# MCU.net
KiCad netlist of a schematic drawn in Altium Designer
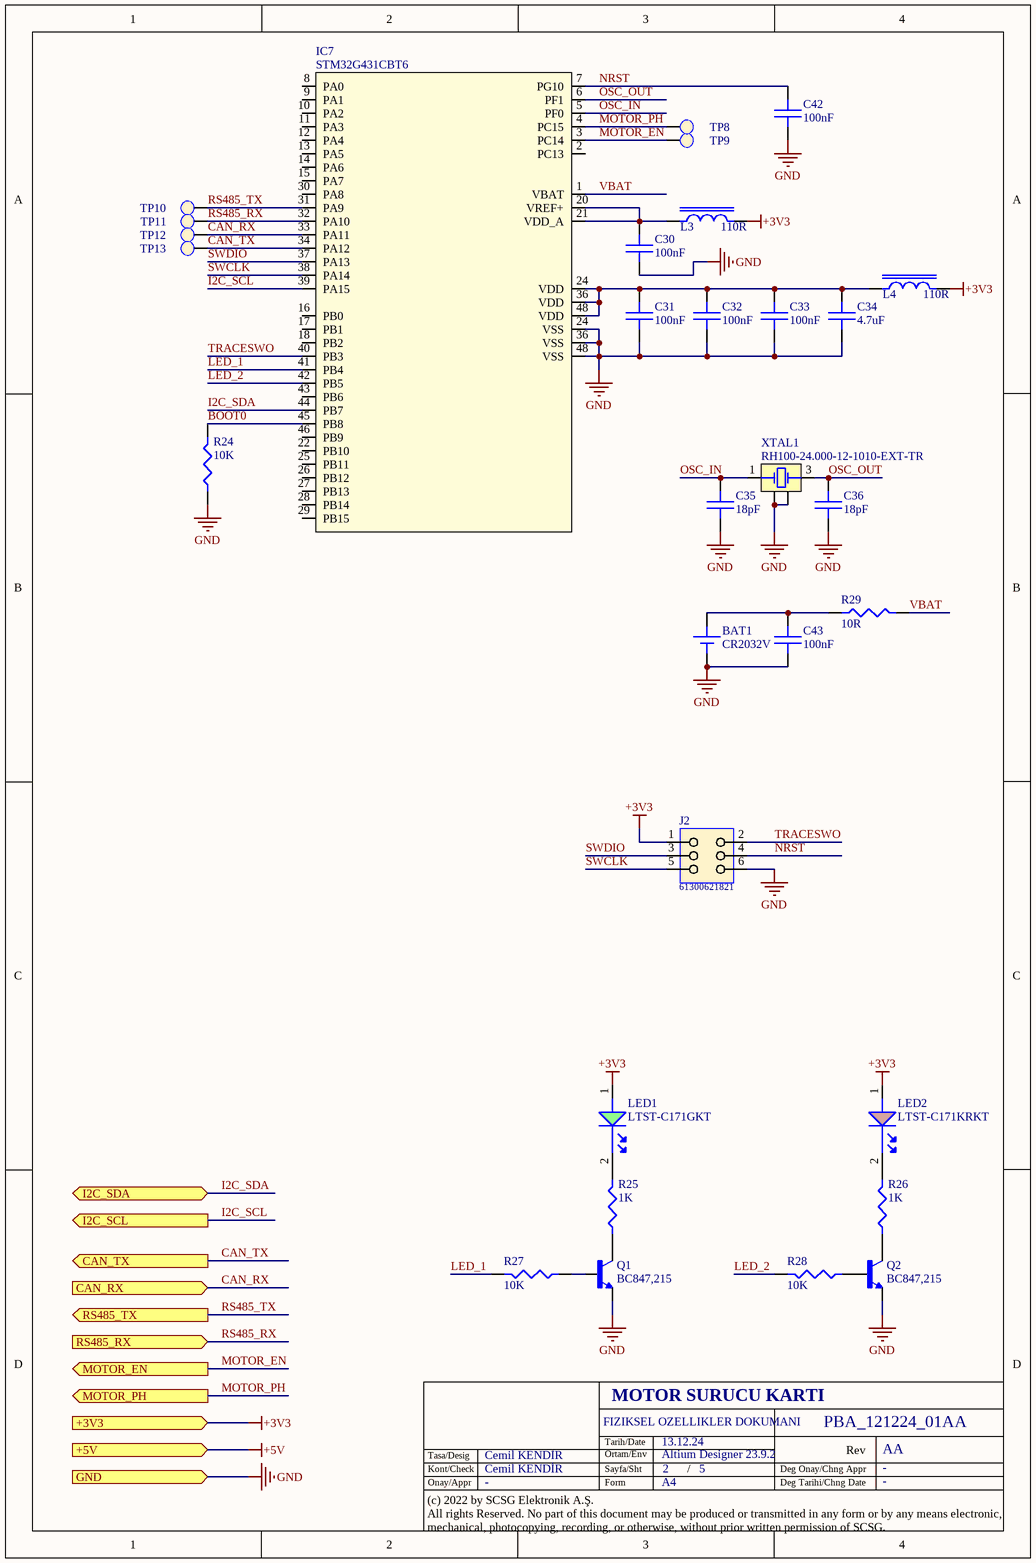
[diagram p0: MCU.SchDoc]

(export (version "E")
  (design (tool "Eeschema 10.0.6"))
  (components
    (comp (ref "BAT1")
      (value "CR2032V")
      (footprint "CR2032V")
      (description "CR2032 Dikey Montaj")
      (fields
        (field (name "MANUFACTURER") "EEMB")
        (field (name "MANUFACTURER PART NUMBER") "CR2032-PEN3-A10606")
      )
      (libsource (lib "Battery") (part "CR2032-PEN3-A10606"))
    )
    (comp (ref "C30")
      (value "100nF")
      (footprint "C0402")
      (description "100nF ,10V ,X7R ,0402")
      (fields
        (field (name "MANUFACTURER") "Yageo")
        (field (name "MANUFACTURER PART NUMBER") "CC0402KRX7R6BB104")
      )
      (libsource (lib "Capacitor") (part "CC0402KRX7R6BB104"))
    )
    (comp (ref "C31")
      (value "100nF")
      (footprint "C0402")
      (description "100nF ,10V ,X7R ,0402")
      (fields
        (field (name "MANUFACTURER") "Yageo")
        (field (name "MANUFACTURER PART NUMBER") "CC0402KRX7R6BB104")
      )
      (libsource (lib "Capacitor") (part "CC0402KRX7R6BB104"))
    )
    (comp (ref "C32")
      (value "100nF")
      (footprint "C0402")
      (description "100nF ,10V ,X7R ,0402")
      (fields
        (field (name "MANUFACTURER") "Yageo")
        (field (name "MANUFACTURER PART NUMBER") "CC0402KRX7R6BB104")
      )
      (libsource (lib "Capacitor") (part "CC0402KRX7R6BB104"))
    )
    (comp (ref "C33")
      (value "100nF")
      (footprint "C0402")
      (description "100nF ,10V ,X7R ,0402")
      (fields
        (field (name "MANUFACTURER") "Yageo")
        (field (name "MANUFACTURER PART NUMBER") "CC0402KRX7R6BB104")
      )
      (libsource (lib "Capacitor") (part "CC0402KRX7R6BB104"))
    )
    (comp (ref "C34")
      (value "4.7uF")
      (footprint "C0603")
      (description "4.7uF, 6.3V, X7R, 0603")
      (fields
        (field (name "MANUFACTURER") "Yageo")
        (field (name "MANUFACTURER PART NUMBER") "CC0603MRX7R5BB475")
      )
      (libsource (lib "Capacitor") (part "CC0603MRX7R5BB475"))
    )
    (comp (ref "C35")
      (value "18pF")
      (footprint "C0402")
      (description "18pF, 50V, C0G, 0402")
      (fields
        (field (name "MANUFACTURER") "Yageo")
        (field (name "MANUFACTURER PART NUMBER") "CC0402JRNPO9BN180")
      )
      (libsource (lib "Capacitor") (part "CC0402JRNPO9BN180"))
    )
    (comp (ref "C36")
      (value "18pF")
      (footprint "C0402")
      (description "18pF, 50V, C0G, 0402")
      (fields
        (field (name "MANUFACTURER") "Yageo")
        (field (name "MANUFACTURER PART NUMBER") "CC0402JRNPO9BN180")
      )
      (libsource (lib "Capacitor") (part "CC0402JRNPO9BN180"))
    )
    (comp (ref "C42")
      (value "100nF")
      (footprint "C0402")
      (description "100nF ,10V ,X7R ,0402")
      (fields
        (field (name "MANUFACTURER") "Yageo")
        (field (name "MANUFACTURER PART NUMBER") "CC0402KRX7R6BB104")
      )
      (libsource (lib "Capacitor") (part "CC0402KRX7R6BB104"))
    )
    (comp (ref "C43")
      (value "100nF")
      (footprint "C0402")
      (description "100nF ,10V ,X7R ,0402")
      (fields
        (field (name "MANUFACTURER") "Yageo")
        (field (name "MANUFACTURER PART NUMBER") "CC0402KRX7R6BB104")
      )
      (libsource (lib "Capacitor") (part "CC0402KRX7R6BB104"))
    )
    (comp (ref "IC7")
      (value "STM32G431CBT6")
      (footprint "LQFP48-7x7mm")
      (description "MCU 32-bit ARM Cortex M4 RISC 128KB Flash 1.8V/2.5V/3.3V 48-Pin LQFP Tray")
      (fields (field (name "MANUFACTURER") "STMicroelectronics"))
      (libsource (lib "IntegratedCircuit") (part "STM32G431CBT6"))
    )
    (comp (ref "J2")
      (value "61300621821")
      (footprint "61300621821")
      (description "Socket Header, THT, pitch 2.54mm, Dual Row, Vertical, 6pin")
      (fields (field (name "MANUFACTURER") "Wurth Electronics"))
      (libsource (lib "Connectors") (part "61300621821"))
    )
    (comp (ref "L3")
      (value "110R")
      (footprint "L0402")
      (description "Ferrite Bead, 0.09 Ohm, 1.2A, 0402;")
      (fields
        (field (name "MANUFACTURER") "Wurth Electronics")
        (field (name "MANUFACTURER PART NUMBER") "74269242111")
      )
      (libsource (lib "Inductor") (part "74269242111"))
    )
    (comp (ref "L4")
      (value "110R")
      (footprint "L0402")
      (description "Ferrite Bead, 0.09 Ohm, 1.2A, 0402;")
      (fields
        (field (name "MANUFACTURER") "Wurth Electronics")
        (field (name "MANUFACTURER PART NUMBER") "74269242111")
      )
      (libsource (lib "Inductor") (part "74269242111"))
    )
    (comp (ref "LED1")
      (value "LTST-C171GKT")
      (footprint "0805_green")
      (description "LED GREEN CLEAR CHIP SMD")
      (fields (field (name "MANUFACTURER") "Vishay Lite-On"))
      (libsource (lib "Diode") (part "LTST-C171GKT"))
    )
    (comp (ref "LED2")
      (value "LTST-C171KRKT")
      (footprint "0805_RED")
      (description "LED RED CLEAR SMD")
      (fields (field (name "MANUFACTURER") "Vishay Lite-On"))
      (libsource (lib "Diode") (part "LTST-C171KRKT"))
    )
    (comp (ref "Q1")
      (value "BC847,215")
      (footprint "SOT23-3")
      (description "TRANS NPN 45V 0.1A SOT23")
      (fields (field (name "MANUFACTURER") "Nexperia"))
      (libsource (lib "Transistor") (part "BC847,215"))
    )
    (comp (ref "Q2")
      (value "BC847,215")
      (footprint "SOT23-3")
      (description "TRANS NPN 45V 0.1A SOT23")
      (fields (field (name "MANUFACTURER") "Nexperia"))
      (libsource (lib "Transistor") (part "BC847,215"))
    )
    (comp (ref "R24")
      (value "10K")
      (footprint "R0402")
      (description "10K, %1, 1/16W, 0402")
      (fields
        (field (name "MANUFACTURER") "YAGEO")
        (field (name "MANUFACTURER PART NUMBER") "RC0402FR-0710KL")
      )
      (libsource (lib "Resistor") (part "RC0402FR-0710KL"))
    )
    (comp (ref "R25")
      (value "1K")
      (footprint "R0402")
      (description "1K, %1, 1/16W, 0402")
      (fields
        (field (name "MANUFACTURER") "YAGEO")
        (field (name "MANUFACTURER PART NUMBER") "RC0402FR-071KL")
      )
      (libsource (lib "Resistor") (part "RC0402FR-071KL"))
    )
    (comp (ref "R26")
      (value "1K")
      (footprint "R0402")
      (description "1K, %1, 1/16W, 0402")
      (fields
        (field (name "MANUFACTURER") "YAGEO")
        (field (name "MANUFACTURER PART NUMBER") "RC0402FR-071KL")
      )
      (libsource (lib "Resistor") (part "RC0402FR-071KL"))
    )
    (comp (ref "R27")
      (value "10K")
      (footprint "R0402")
      (description "10K, %1, 1/16W, 0402")
      (fields
        (field (name "MANUFACTURER") "YAGEO")
        (field (name "MANUFACTURER PART NUMBER") "RC0402FR-0710KL")
      )
      (libsource (lib "Resistor") (part "RC0402FR-0710KL"))
    )
    (comp (ref "R28")
      (value "10K")
      (footprint "R0402")
      (description "10K, %1, 1/16W, 0402")
      (fields
        (field (name "MANUFACTURER") "YAGEO")
        (field (name "MANUFACTURER PART NUMBER") "RC0402FR-0710KL")
      )
      (libsource (lib "Resistor") (part "RC0402FR-0710KL"))
    )
    (comp (ref "R29")
      (value "10R")
      (footprint "R0402")
      (description "10R, %1, 1/16W, 0402")
      (fields
        (field (name "MANUFACTURER") "YAGEO")
        (field (name "MANUFACTURER PART NUMBER") "RC0402FR-0710RL")
      )
      (libsource (lib "Resistor") (part "RC0402FR-0710RL"))
    )
    (comp (ref "TP8")
      (value "TestPoint1")
      (footprint "SMD_1mmPoint")
      (description "test ölçüm noktası")
      (fields (field (name "MANUFACTURER") "NO BOM DEVICE"))
      (libsource (lib "Connectors") (part "TestPoint1"))
    )
    (comp (ref "TP9")
      (value "TestPoint1")
      (footprint "SMD_1mmPoint")
      (description "test ölçüm noktası")
      (fields (field (name "MANUFACTURER") "NO BOM DEVICE"))
      (libsource (lib "Connectors") (part "TestPoint1"))
    )
    (comp (ref "TP10")
      (value "TestPoint1")
      (footprint "SMD_1mmPoint")
      (description "test ölçüm noktası")
      (fields (field (name "MANUFACTURER") "NO BOM DEVICE"))
      (libsource (lib "Connectors") (part "TestPoint1"))
    )
    (comp (ref "TP11")
      (value "TestPoint1")
      (footprint "SMD_1mmPoint")
      (description "test ölçüm noktası")
      (fields (field (name "MANUFACTURER") "NO BOM DEVICE"))
      (libsource (lib "Connectors") (part "TestPoint1"))
    )
    (comp (ref "TP12")
      (value "TestPoint1")
      (footprint "SMD_1mmPoint")
      (description "test ölçüm noktası")
      (fields (field (name "MANUFACTURER") "NO BOM DEVICE"))
      (libsource (lib "Connectors") (part "TestPoint1"))
    )
    (comp (ref "TP13")
      (value "TestPoint1")
      (footprint "SMD_1mmPoint")
      (description "test ölçüm noktası")
      (fields (field (name "MANUFACTURER") "NO BOM DEVICE"))
      (libsource (lib "Connectors") (part "TestPoint1"))
    )
    (comp (ref "XTAL1")
      (value "RH100-24.000-12-1010-EXT-TR")
      (footprint "WE-XTAL_CFPX-180")
      (description "Crystal, 24Mhz, 12Pf, Smd, 3.2Mm X 2.5Mm Rohs Compliant: Yes ¦Raltron RH100-24.000-12-1010-EXT-TR")
      (fields (field (name "MANUFACTURER") "Raltron Electronics"))
      (libsource (lib "Oscilator") (part "RH100-24.000-12-1010-EXT-TR"))
    )
  )
  (nets
    (net (code "1") (name "+3V3") (class "Default")
      (node (ref "J2") (pin "1") (pinfunction "1_1") (pintype "passive"))
      (node (ref "L3") (pin "2") (pinfunction "2_2") (pintype "passive"))
      (node (ref "L4") (pin "2") (pinfunction "2_2") (pintype "passive"))
      (node (ref "LED1") (pin "1") (pinfunction "1_1") (pintype "passive"))
      (node (ref "LED2") (pin "1") (pinfunction "1_1") (pintype "passive"))
    )
    (net (code "3") (name "/BOOT0") (class "Default")
      (node (ref "IC7") (pin "45") (pinfunction "PB8_45") (pintype "passive"))
      (node (ref "R24") (pin "2") (pinfunction "2_2") (pintype "passive"))
    )
    (net (code "4") (name "/CAN_RX") (class "Default")
      (node (ref "IC7") (pin "33") (pinfunction "PA11_33") (pintype "passive"))
      (node (ref "TP12") (pin "1") (pinfunction "1_1") (pintype "passive"))
    )
    (net (code "5") (name "/CAN_TX") (class "Default")
      (node (ref "IC7") (pin "34") (pinfunction "PA12_34") (pintype "passive"))
      (node (ref "TP13") (pin "1") (pinfunction "1_1") (pintype "passive"))
    )
    (net (code "6") (name "/I2C_SCL") (class "Default")
      (node (ref "IC7") (pin "39") (pinfunction "PA15_39") (pintype "passive"))
    )
    (net (code "7") (name "/I2C_SDA") (class "Default")
      (node (ref "IC7") (pin "44") (pinfunction "PB7_44") (pintype "passive"))
    )
    (net (code "8") (name "/LED_1") (class "Default")
      (node (ref "IC7") (pin "41") (pinfunction "PB4_41") (pintype "passive"))
      (node (ref "R27") (pin "2") (pinfunction "2_2") (pintype "passive"))
    )
    (net (code "9") (name "/LED_2") (class "Default")
      (node (ref "IC7") (pin "42") (pinfunction "PB5_42") (pintype "passive"))
      (node (ref "R28") (pin "2") (pinfunction "2_2") (pintype "passive"))
    )
    (net (code "10") (name "/MOTOR_EN") (class "Default")
      (node (ref "IC7") (pin "3") (pinfunction "PC14_3") (pintype "passive"))
      (node (ref "TP9") (pin "1") (pinfunction "1_1") (pintype "passive"))
    )
    (net (code "11") (name "/MOTOR_PH") (class "Default")
      (node (ref "IC7") (pin "4") (pinfunction "PC15_4") (pintype "passive"))
      (node (ref "TP8") (pin "1") (pinfunction "1_1") (pintype "passive"))
    )
    (net (code "12") (name "/NRST") (class "Default")
      (node (ref "C42") (pin "2") (pintype "passive"))
      (node (ref "IC7") (pin "7") (pinfunction "PG10_7") (pintype "passive"))
      (node (ref "J2") (pin "4") (pinfunction "4_4") (pintype "passive"))
    )
    (net (code "13") (name "/OSC_IN") (class "Default")
      (node (ref "C35") (pin "2") (pintype "passive"))
      (node (ref "IC7") (pin "5") (pinfunction "PF0_5") (pintype "passive"))
      (node (ref "XTAL1") (pin "1") (pinfunction "Crystal_1") (pintype "passive"))
    )
    (net (code "14") (name "/OSC_OUT") (class "Default")
      (node (ref "C36") (pin "2") (pintype "passive"))
      (node (ref "IC7") (pin "6") (pinfunction "PF1_6") (pintype "passive"))
      (node (ref "XTAL1") (pin "3") (pinfunction "Crystal_3") (pintype "passive"))
    )
    (net (code "15") (name "/RS485_RX") (class "Default")
      (node (ref "IC7") (pin "32") (pinfunction "PA10_32") (pintype "passive"))
      (node (ref "TP11") (pin "1") (pinfunction "1_1") (pintype "passive"))
    )
    (net (code "16") (name "/RS485_TX") (class "Default")
      (node (ref "IC7") (pin "31") (pinfunction "PA9_31") (pintype "passive"))
      (node (ref "TP10") (pin "1") (pinfunction "1_1") (pintype "passive"))
    )
    (net (code "17") (name "/SWCLK") (class "Default")
      (node (ref "IC7") (pin "38") (pinfunction "PA14_38") (pintype "passive"))
      (node (ref "J2") (pin "5") (pinfunction "5_5") (pintype "passive"))
    )
    (net (code "18") (name "/SWDIO") (class "Default")
      (node (ref "IC7") (pin "37") (pinfunction "PA13_37") (pintype "passive"))
      (node (ref "J2") (pin "3") (pinfunction "3_3") (pintype "passive"))
    )
    (net (code "19") (name "/TRACESWO") (class "Default")
      (node (ref "IC7") (pin "40") (pinfunction "PB3_40") (pintype "passive"))
      (node (ref "J2") (pin "2") (pinfunction "2_2") (pintype "passive"))
    )
    (net (code "20") (name "/VBAT") (class "Default")
      (node (ref "IC7") (pin "1") (pinfunction "VBAT_1") (pintype "passive"))
      (node (ref "R29") (pin "2") (pinfunction "2_2") (pintype "passive"))
    )
    (net (code "21") (name "GND") (class "Default")
      (node (ref "BAT1") (pin "2") (pinfunction "2_2") (pintype "passive"))
      (node (ref "C30") (pin "1") (pintype "passive"))
      (node (ref "C31") (pin "1") (pintype "passive"))
      (node (ref "C32") (pin "1") (pintype "passive"))
      (node (ref "C33") (pin "1") (pintype "passive"))
      (node (ref "C34") (pin "1") (pintype "passive"))
      (node (ref "C35") (pin "1") (pintype "passive"))
      (node (ref "C36") (pin "1") (pintype "passive"))
      (node (ref "C42") (pin "1") (pintype "passive"))
      (node (ref "C43") (pin "1") (pintype "passive"))
      (node (ref "IC7") (pin "24") (pinfunction "VSS_24") (pintype "passive"))
      (node (ref "IC7") (pin "36") (pinfunction "VSS_36") (pintype "passive"))
      (node (ref "IC7") (pin "48") (pinfunction "VSS_48") (pintype "passive"))
      (node (ref "J2") (pin "6") (pinfunction "6_6") (pintype "passive"))
      (node (ref "Q1") (pin "2") (pinfunction "E_2") (pintype "passive"))
      (node (ref "Q2") (pin "2") (pinfunction "E_2") (pintype "passive"))
      (node (ref "R24") (pin "1") (pinfunction "1_1") (pintype "passive"))
      (node (ref "XTAL1") (pin "2") (pinfunction "GND_&_Lid_2") (pintype "passive"))
      (node (ref "XTAL1") (pin "4") (pinfunction "GND_&_Lid_4") (pintype "passive"))
    )
    (net (code "22") (name "Net-(BAT1-Pad1)") (class "Default")
      (node (ref "BAT1") (pin "1") (pinfunction "1_1") (pintype "passive"))
      (node (ref "C43") (pin "2") (pintype "passive"))
      (node (ref "R29") (pin "1") (pinfunction "1_1") (pintype "passive"))
    )
    (net (code "23") (name "Net-(C31-Pad2)") (class "Default")
      (node (ref "C31") (pin "2") (pintype "passive"))
      (node (ref "C32") (pin "2") (pintype "passive"))
      (node (ref "C33") (pin "2") (pintype "passive"))
      (node (ref "C34") (pin "2") (pintype "passive"))
      (node (ref "IC7") (pin "24") (pinfunction "VDD_24") (pintype "passive"))
      (node (ref "IC7") (pin "36") (pinfunction "VDD_36") (pintype "passive"))
      (node (ref "IC7") (pin "48") (pinfunction "VDD_48") (pintype "passive"))
      (node (ref "L4") (pin "1") (pinfunction "1_1") (pintype "passive"))
    )
    (net (code "24") (name "Net-(IC7-VDD_A)") (class "Default")
      (node (ref "C30") (pin "2") (pintype "passive"))
      (node (ref "IC7") (pin "20") (pinfunction "VREF+_20") (pintype "passive"))
      (node (ref "IC7") (pin "21") (pinfunction "VDD_A_21") (pintype "passive"))
      (node (ref "L3") (pin "1") (pinfunction "1_1") (pintype "passive"))
    )
    (net (code "25") (name "Net-(LED1-Pad2)") (class "Default")
      (node (ref "LED1") (pin "2") (pinfunction "2_2") (pintype "passive"))
      (node (ref "R25") (pin "2") (pinfunction "2_2") (pintype "passive"))
    )
    (net (code "26") (name "Net-(LED2-Pad2)") (class "Default")
      (node (ref "LED2") (pin "2") (pinfunction "2_2") (pintype "passive"))
      (node (ref "R26") (pin "2") (pinfunction "2_2") (pintype "passive"))
    )
    (net (code "27") (name "Net-(Q1-B)") (class "Default")
      (node (ref "Q1") (pin "1") (pinfunction "B_1") (pintype "passive"))
      (node (ref "R27") (pin "1") (pinfunction "1_1") (pintype "passive"))
    )
    (net (code "28") (name "Net-(Q1-C)") (class "Default")
      (node (ref "Q1") (pin "3") (pinfunction "C_3") (pintype "passive"))
      (node (ref "R25") (pin "1") (pinfunction "1_1") (pintype "passive"))
    )
    (net (code "29") (name "Net-(Q2-B)") (class "Default")
      (node (ref "Q2") (pin "1") (pinfunction "B_1") (pintype "passive"))
      (node (ref "R28") (pin "1") (pinfunction "1_1") (pintype "passive"))
    )
    (net (code "30") (name "Net-(Q2-C)") (class "Default")
      (node (ref "Q2") (pin "3") (pinfunction "C_3") (pintype "passive"))
      (node (ref "R26") (pin "1") (pinfunction "1_1") (pintype "passive"))
    )
    (net (code "31") (name "unconnected-(IC7-PA0-Pad8)") (class "Default")
      (node (ref "IC7") (pin "8") (pinfunction "PA0_8") (pintype "passive"))
    )
    (net (code "32") (name "unconnected-(IC7-PA1-Pad9)") (class "Default")
      (node (ref "IC7") (pin "9") (pinfunction "PA1_9") (pintype "passive"))
    )
    (net (code "33") (name "unconnected-(IC7-PA2-Pad10)") (class "Default")
      (node (ref "IC7") (pin "10") (pinfunction "PA2_10") (pintype "passive"))
    )
    (net (code "34") (name "unconnected-(IC7-PA3-Pad11)") (class "Default")
      (node (ref "IC7") (pin "11") (pinfunction "PA3_11") (pintype "passive"))
    )
    (net (code "35") (name "unconnected-(IC7-PA4-Pad12)") (class "Default")
      (node (ref "IC7") (pin "12") (pinfunction "PA4_12") (pintype "passive"))
    )
    (net (code "36") (name "unconnected-(IC7-PA5-Pad13)") (class "Default")
      (node (ref "IC7") (pin "13") (pinfunction "PA5_13") (pintype "passive"))
    )
    (net (code "37") (name "unconnected-(IC7-PA6-Pad14)") (class "Default")
      (node (ref "IC7") (pin "14") (pinfunction "PA6_14") (pintype "passive"))
    )
    (net (code "38") (name "unconnected-(IC7-PA7-Pad15)") (class "Default")
      (node (ref "IC7") (pin "15") (pinfunction "PA7_15") (pintype "passive"))
    )
    (net (code "39") (name "unconnected-(IC7-PA8-Pad30)") (class "Default")
      (node (ref "IC7") (pin "30") (pinfunction "PA8_30") (pintype "passive"))
    )
    (net (code "40") (name "unconnected-(IC7-PB0-Pad16)") (class "Default")
      (node (ref "IC7") (pin "16") (pinfunction "PB0_16") (pintype "passive"))
    )
    (net (code "41") (name "unconnected-(IC7-PB1-Pad17)") (class "Default")
      (node (ref "IC7") (pin "17") (pinfunction "PB1_17") (pintype "passive"))
    )
    (net (code "42") (name "unconnected-(IC7-PB2-Pad18)") (class "Default")
      (node (ref "IC7") (pin "18") (pinfunction "PB2_18") (pintype "passive"))
    )
    (net (code "43") (name "unconnected-(IC7-PB6-Pad43)") (class "Default")
      (node (ref "IC7") (pin "43") (pinfunction "PB6_43") (pintype "passive"))
    )
    (net (code "44") (name "unconnected-(IC7-PB9-Pad46)") (class "Default")
      (node (ref "IC7") (pin "46") (pinfunction "PB9_46") (pintype "passive"))
    )
    (net (code "45") (name "unconnected-(IC7-PB10-Pad22)") (class "Default")
      (node (ref "IC7") (pin "22") (pinfunction "PB10_22") (pintype "passive"))
    )
    (net (code "46") (name "unconnected-(IC7-PB11-Pad25)") (class "Default")
      (node (ref "IC7") (pin "25") (pinfunction "PB11_25") (pintype "passive"))
    )
    (net (code "47") (name "unconnected-(IC7-PB12-Pad26)") (class "Default")
      (node (ref "IC7") (pin "26") (pinfunction "PB12_26") (pintype "passive"))
    )
    (net (code "48") (name "unconnected-(IC7-PB13-Pad27)") (class "Default")
      (node (ref "IC7") (pin "27") (pinfunction "PB13_27") (pintype "passive"))
    )
    (net (code "49") (name "unconnected-(IC7-PB14-Pad28)") (class "Default")
      (node (ref "IC7") (pin "28") (pinfunction "PB14_28") (pintype "passive"))
    )
    (net (code "50") (name "unconnected-(IC7-PB15-Pad29)") (class "Default")
      (node (ref "IC7") (pin "29") (pinfunction "PB15_29") (pintype "passive"))
    )
    (net (code "51") (name "unconnected-(IC7-PC13-Pad2)") (class "Default")
      (node (ref "IC7") (pin "2") (pinfunction "PC13_2") (pintype "passive"))
    )
  )
)
